# singleInverter.net
KiCad netlist of a schematic drawn in EAGLE
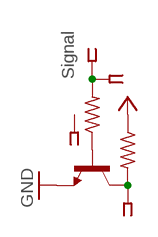
[diagram p0: schematic, sheet 1]

(export (version "E")
  (design (tool "Eeschema 10.0.6"))
  (components
    (comp (ref "NO_INVERT_JUMPER2")
      (value "SSW-103-02-G-S")
      (footprint "eagle-import:SSW-103-02-G-S")
      (fields (field (name "MF") "Samtec Inc."))
      (libsource (lib "eagle-import") (part "SSW-103-02-G-S"))
    )
    (comp (ref "R4")
      (value "~220")
      (footprint "eagle-import:0204_7")
      (libsource (lib "eagle-import") (part "R-US_0204/7"))
    )
    (comp (ref "R5")
      (value "~220")
      (footprint "eagle-import:0204_7")
      (libsource (lib "eagle-import") (part "R-US_0204/7"))
    )
    (comp (ref "SIGS_IN")
      (value "SSW-106-02-G-D")
      (footprint "eagle-import:SSW-106-02-G-D")
      (fields (field (name "MF") "Samtec Inc."))
      (libsource (lib "eagle-import") (part "SSW-106-02-G-D"))
    )
    (comp (ref "T3")
      (value "2N3565")
      (footprint "eagle-import:TO92")
      (libsource (lib "eagle-import") (part "2N3565"))
    )
  )
  (nets
    (net (code "1") (name "GND") (class "Default")
      (node (ref "T3") (pin "3") (pinfunction "E_3") (pintype "passive"))
    )
    (net (code "2") (name "Net-(NO_INVERT_JUMPER2B-1)") (class "Default")
      (node (ref "NO_INVERT_JUMPER2") (pin "2") (pinfunction "1_2") (pintype "passive"))
      (node (ref "R4") (pin "2") (pinfunction "2_2") (pintype "passive"))
      (node (ref "SIGS_IN") (pin "8") (pinfunction "1_8") (pintype "passive"))
    )
    (net (code "3") (name "Net-(NO_INVERT_JUMPER2C-1)") (class "Default")
      (node (ref "NO_INVERT_JUMPER2") (pin "3") (pinfunction "1_3") (pintype "passive"))
      (node (ref "R5") (pin "2") (pinfunction "2_2") (pintype "passive"))
      (node (ref "T3") (pin "1") (pinfunction "C_1") (pintype "passive"))
    )
    (net (code "4") (name "Net-(T3-B)") (class "Default")
      (node (ref "R4") (pin "1") (pinfunction "1_1") (pintype "passive"))
      (node (ref "T3") (pin "2") (pinfunction "B_2") (pintype "passive"))
    )
    (net (code "5") (name "VCC") (class "Default")
      (node (ref "R5") (pin "1") (pinfunction "1_1") (pintype "passive"))
    )
    (net (code "6") (name "unconnected-(NO_INVERT_JUMPER2-Pad1)") (class "Default")
      (node (ref "NO_INVERT_JUMPER2") (pin "1") (pinfunction "1_1") (pintype "passive"))
    )
  )
)
